# weather-cube_sensor_sht31d.net
KiCad netlist of a schematic drawn in EAGLE
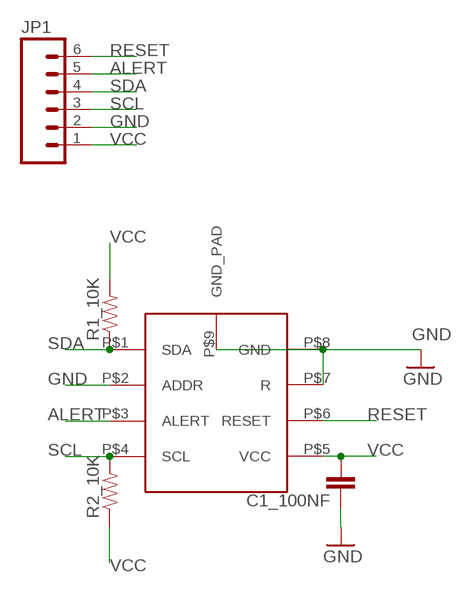
[diagram p0: schematic, sheet 1]

(export (version "E")
  (design (tool "Eeschema 10.0.6"))
  (components
    (comp (ref "C1_100NF")
      (value "CAP0603-CAP")
      (footprint "eagle-import:0603-CAP")
      (libsource (lib "eagle-import") (part "CAP0603-CAP"))
    )
    (comp (ref "JP1")
      (value "M06SILK_FEMALE_PTH")
      (footprint "eagle-import:1X06")
      (libsource (lib "eagle-import") (part "M06SILK_FEMALE_PTH"))
    )
    (comp (ref "R1_10K")
      (value "RESISTOR0603-RES")
      (footprint "eagle-import:0603-RES")
      (libsource (lib "eagle-import") (part "RESISTOR0603-RES"))
    )
    (comp (ref "R2_10K")
      (value "RESISTOR0603-RES")
      (footprint "eagle-import:0603-RES")
      (libsource (lib "eagle-import") (part "RESISTOR0603-RES"))
    )
    (comp (ref "U$1")
      (value "SHT31-D")
      (footprint "eagle-import:SHT31-D")
      (libsource (lib "eagle-import") (part "SHT31-D"))
    )
  )
  (nets
    (net (code "1") (name "/ALERT") (class "Default")
      (node (ref "JP1") (pin "5") (pinfunction "5_5") (pintype "passive"))
      (node (ref "U$1") (pin "P$3") (pinfunction "ALERT_P$3") (pintype "bidirectional"))
    )
    (net (code "2") (name "/RESET") (class "Default")
      (node (ref "JP1") (pin "6") (pinfunction "6_6") (pintype "passive"))
      (node (ref "U$1") (pin "P$6") (pinfunction "RESET_P$6") (pintype "bidirectional"))
    )
    (net (code "3") (name "/SCL") (class "Default")
      (node (ref "JP1") (pin "3") (pinfunction "3_3") (pintype "passive"))
      (node (ref "R2_10K") (pin "2") (pinfunction "2_2") (pintype "passive"))
      (node (ref "U$1") (pin "P$4") (pinfunction "SCL_P$4") (pintype "bidirectional"))
    )
    (net (code "4") (name "/SDA") (class "Default")
      (node (ref "JP1") (pin "4") (pinfunction "4_4") (pintype "passive"))
      (node (ref "R1_10K") (pin "1") (pinfunction "1_1") (pintype "passive"))
      (node (ref "U$1") (pin "P$1") (pinfunction "SDA_P$1") (pintype "bidirectional"))
    )
    (net (code "5") (name "/VCC") (class "Default")
      (node (ref "C1_100NF") (pin "2") (pinfunction "2_2") (pintype "passive"))
      (node (ref "JP1") (pin "1") (pinfunction "1_1") (pintype "passive"))
      (node (ref "R1_10K") (pin "2") (pinfunction "2_2") (pintype "passive"))
      (node (ref "R2_10K") (pin "1") (pinfunction "1_1") (pintype "passive"))
      (node (ref "U$1") (pin "P$5") (pinfunction "VCC_P$5") (pintype "bidirectional"))
    )
    (net (code "6") (name "GND") (class "Default")
      (node (ref "C1_100NF") (pin "1") (pinfunction "1_1") (pintype "passive"))
      (node (ref "JP1") (pin "2") (pinfunction "2_2") (pintype "passive"))
      (node (ref "U$1") (pin "P$2") (pinfunction "ADDR_P$2") (pintype "bidirectional"))
      (node (ref "U$1") (pin "P$7") (pinfunction "R_P$7") (pintype "bidirectional"))
      (node (ref "U$1") (pin "P$8") (pinfunction "GND_P$8") (pintype "bidirectional"))
      (node (ref "U$1") (pin "P$9") (pinfunction "GND_PAD_P$9") (pintype "bidirectional"))
    )
  )
)
